# TTR87557913_done.net
KiCad netlist of a schematic drawn in Altium Designer
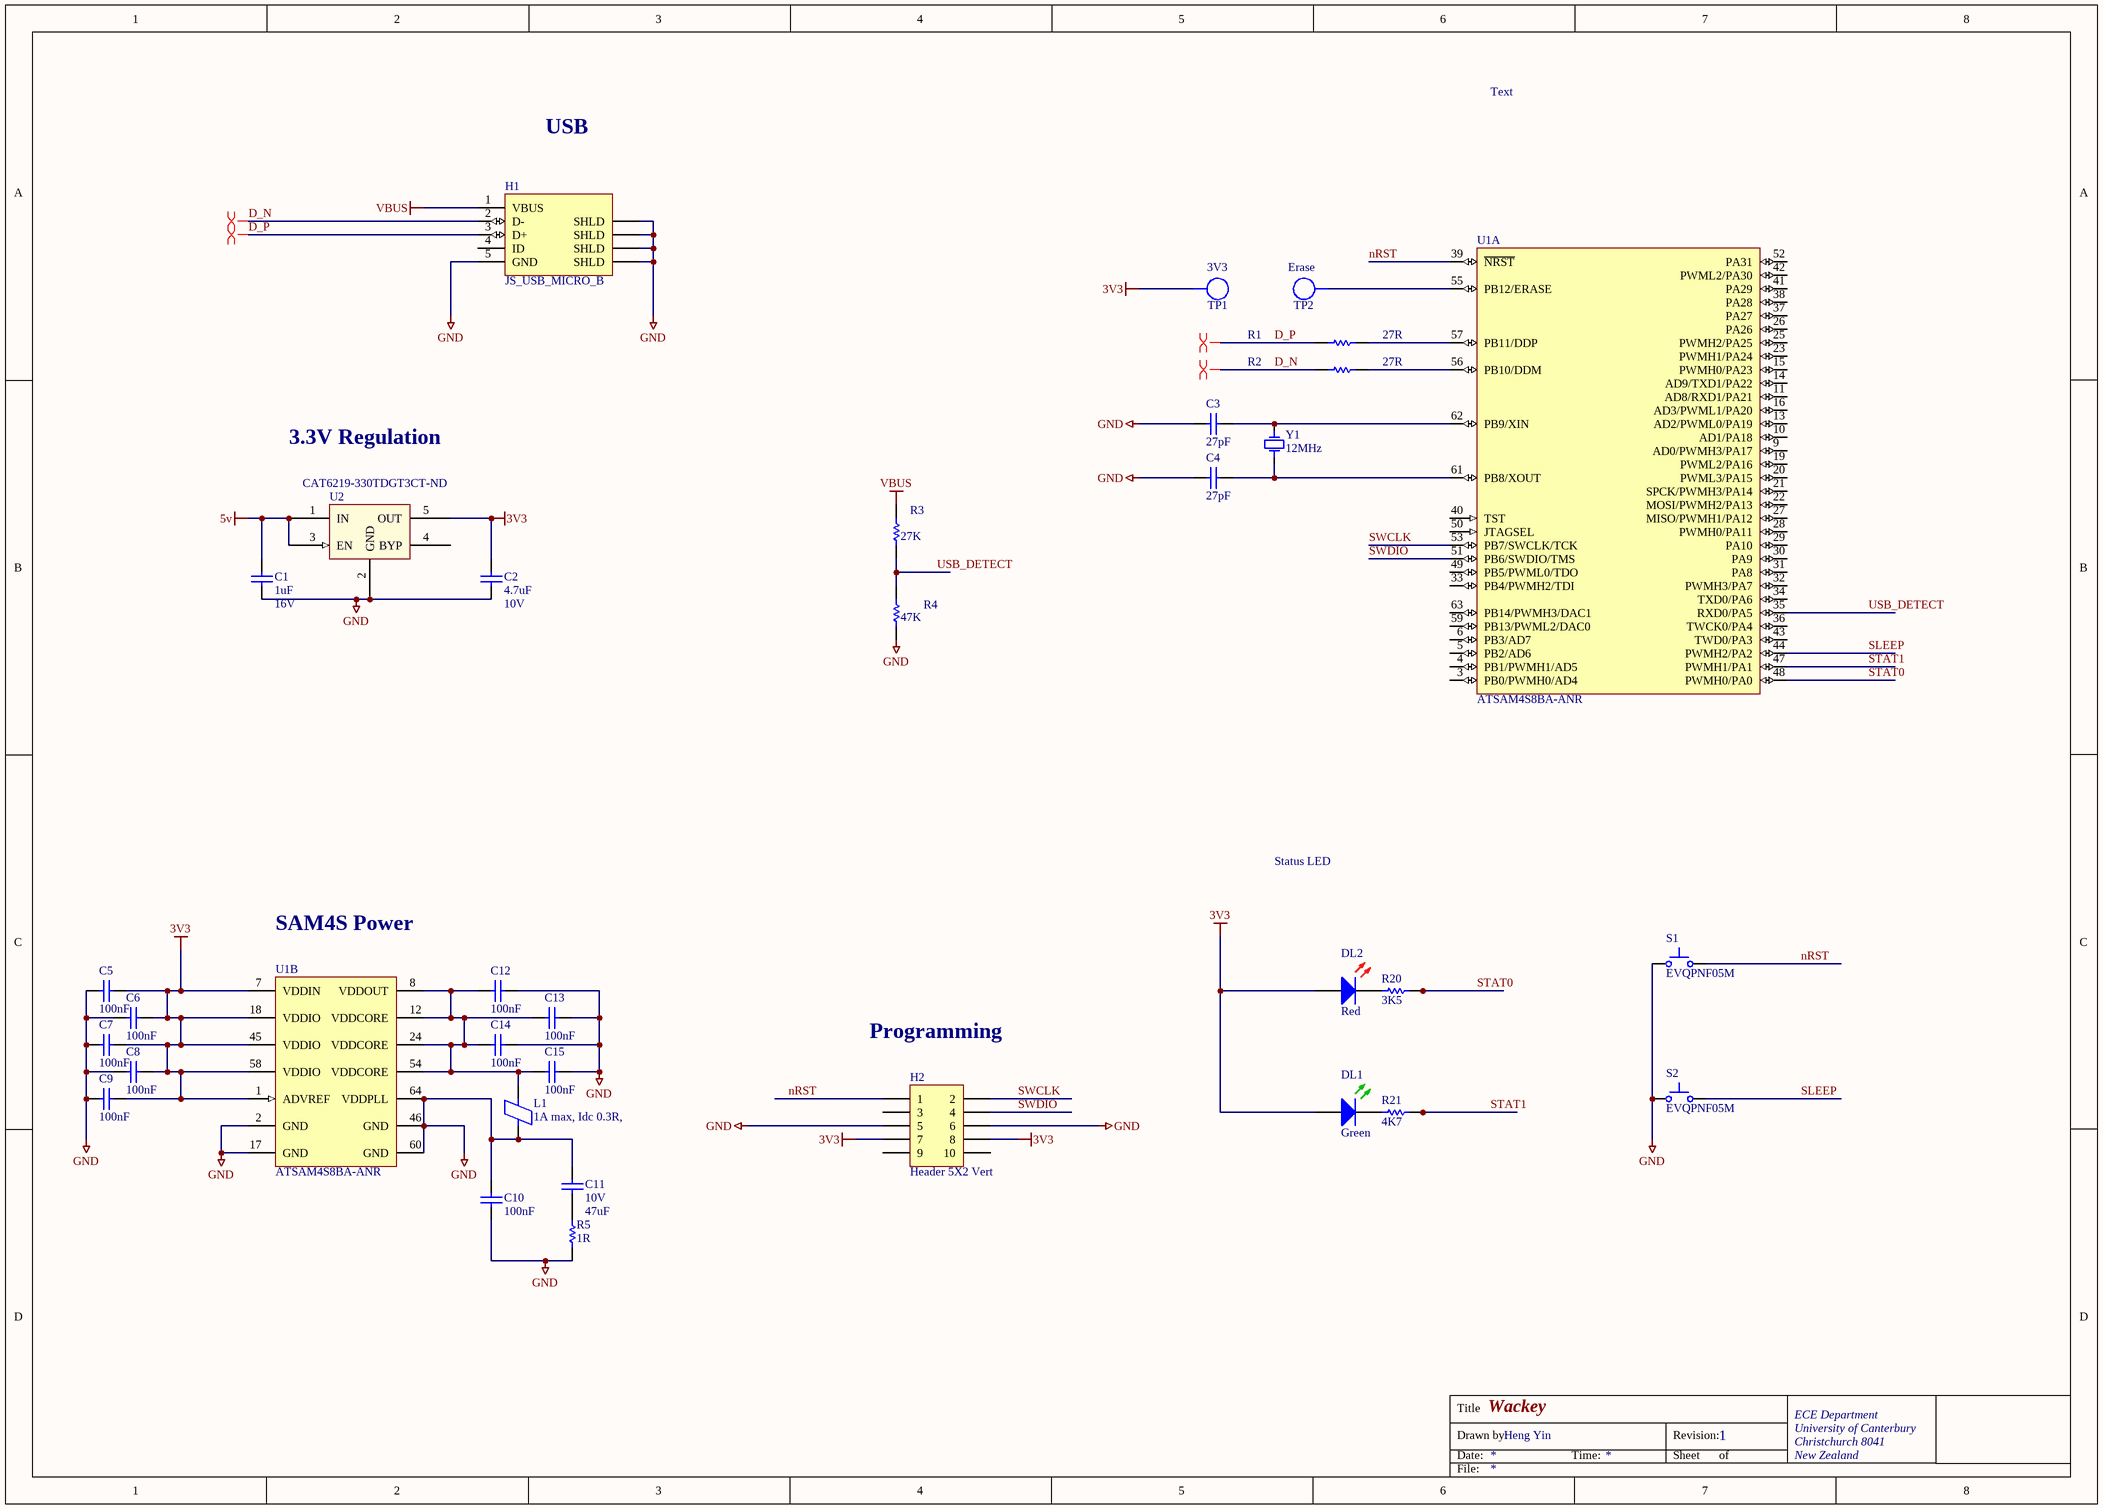
[diagram p0: TTR87557913_done.SchDoc]

(export (version "E")
  (design (tool "Eeschema 10.0.6"))
  (components
    (comp (ref "C1")
      (value "1uF")
      (footprint "CAPC1608L")
      (description "CAP CER 1uF Y5V -20% +80% 16V 0603")
      (fields (field (name "MAX VOLTAGE") "16V"))
      (libsource (lib "ECE AD19Components_22V1") (part "CC_1uF_0603"))
    )
    (comp (ref "C2")
      (value "4.7uF")
      (footprint "CAPC1608N")
      (description "CAP CER 4.7uF X5R +-20%  10V 0603")
      (fields (field (name "MAX VOLTAGE") "10V"))
      (libsource (lib "ECE AD19Components_22V1") (part "CC_4.7uF_0603"))
    )
    (comp (ref "C3")
      (value "27pF")
      (footprint "CAPC1608L")
      (description "CAP CER 27pF NPO/COG +-5% 50V 0603")
      (libsource (lib "ECE AD19Components_22V1") (part "CC_27pF_0603"))
    )
    (comp (ref "C4")
      (value "27pF")
      (footprint "CAPC1608L")
      (description "CAP CER 27pF NPO/COG +-5% 50V 0603")
      (libsource (lib "ECE AD19Components_22V1") (part "CC_27pF_0603"))
    )
    (comp (ref "C5")
      (value "100nF")
      (footprint "CAPC1608L")
      (description "CAP CER 100nF X7R +-10% 50V 0603")
      (libsource (lib "ECE AD19Components_22V1") (part "CC_100nF_0603"))
    )
    (comp (ref "C6")
      (value "100nF")
      (footprint "CAPC1608L")
      (description "CAP CER 100nF X7R +-10% 50V 0603")
      (libsource (lib "ECE AD19Components_22V1") (part "CC_100nF_0603"))
    )
    (comp (ref "C7")
      (value "100nF")
      (footprint "CAPC1608L")
      (description "CAP CER 100nF X7R +-10% 50V 0603")
      (libsource (lib "ECE AD19Components_22V1") (part "CC_100nF_0603"))
    )
    (comp (ref "C8")
      (value "100nF")
      (footprint "CAPC1608L")
      (description "CAP CER 100nF X7R +-10% 50V 0603")
      (libsource (lib "ECE AD19Components_22V1") (part "CC_100nF_0603"))
    )
    (comp (ref "C9")
      (value "100nF")
      (footprint "CAPC1608L")
      (description "CAP CER 100nF X7R +-10% 50V 0603")
      (libsource (lib "ECE AD19Components_22V1") (part "CC_100nF_0603"))
    )
    (comp (ref "C10")
      (value "100nF")
      (footprint "CAPC1608L")
      (description "CAP CER 100nF X7R +-10% 50V 0603")
      (libsource (lib "ECE AD19Components_22V1") (part "CC_100nF_0603"))
    )
    (comp (ref "C11")
      (value "47uF")
      (footprint "CAPC3216L")
      (description "CAP CER 47uF X5R -/+20% 10V 1206")
      (fields (field (name "MAX VOLTAGE") "10V"))
      (libsource (lib "ECE AD19Components_22V1") (part "CC_47uF_1206"))
    )
    (comp (ref "C12")
      (value "100nF")
      (footprint "CAPC1608L")
      (description "CAP CER 100nF X7R +-10% 50V 0603")
      (libsource (lib "ECE AD19Components_22V1") (part "CC_100nF_0603"))
    )
    (comp (ref "C13")
      (value "100nF")
      (footprint "CAPC1608L")
      (description "CAP CER 100nF X7R +-10% 50V 0603")
      (libsource (lib "ECE AD19Components_22V1") (part "CC_100nF_0603"))
    )
    (comp (ref "C14")
      (value "100nF")
      (footprint "CAPC1608L")
      (description "CAP CER 100nF X7R +-10% 50V 0603")
      (libsource (lib "ECE AD19Components_22V1") (part "CC_100nF_0603"))
    )
    (comp (ref "C15")
      (value "100nF")
      (footprint "CAPC1608L")
      (description "CAP CER 100nF X7R +-10% 50V 0603")
      (libsource (lib "ECE AD19Components_22V1") (part "CC_100nF_0603"))
    )
    (comp (ref "DL1")
      (value "Green")
      (footprint "WL-SMCW0603")
      (description "LED Green 430mcd 0603 SMD")
      (fields
        (field (name "MANUFACTURER") "WURTH ELEKTRONIK")
        (field (name "MANUFACTURER PART NUMBER") "150060GS75000")
        (field (name "LED COLOUR") "Green")
      )
      (libsource (lib "ECE AD19Components_22V1") (part "DL_150060GS75000"))
    )
    (comp (ref "DL2")
      (value "Red")
      (footprint "WL-SMCW0603")
      (description "LED Red 250mcd 0603 SMD")
      (fields
        (field (name "MANUFACTURER") "WURTH ELEKTRONIK")
        (field (name "MANUFACTURER PART NUMBER") "150060RS75000")
        (field (name "LED COLOUR") "Red")
      )
      (libsource (lib "ECE AD19Components_22V1") (part "DL_150060RS75000"))
    )
    (comp (ref "H1")
      (value "JS_USB_MICRO_B")
      (footprint "FCI_USB_10118194-0001LF")
      (description "CONN USB MICRO B RECPT SMT R/A")
      (fields (field (name "MANUFACTURER") "FCI") (field (name "MANUFACTURER PART NUMBER") "10118194-0001LF"))
      (libsource (lib "ECE AD19Components_22V1") (part "JS_USB_MICRO_B_SMT"))
    )
    (comp (ref "H2")
      (value "Header 5X2 Vert")
      (footprint "IDC2.54-V10D")
      (description "IDC Header, 2,54mm, 10-Pin, Vert")
      (libsource (lib "ECE AD19Components_22V1") (part "JA_HDR_IDC_5X2_VERT"))
    )
    (comp (ref "L1")
      (value "1A max, Idc 0.3R,")
      (footprint "INDC3216L")
      (description "Ferrite Bead, Rdc 0.3R, Z100MHZ 600R, Imax 1A, SMD 1206")
      (fields
        (field (name "MANUFACTURER") "FAIR-RITE")
        (field (name "MANUFACTURER PART NUMBER") "2512066017Y1")
      )
      (libsource (lib "ECE AD19Components_22V1") (part "IN_Ferrite-Bead"))
    )
    (comp (ref "R1")
      (value "27R")
      (footprint "RESC1608L")
      (description "RES 27 OHM 1/10W 5% 0603 SMD")
      (libsource (lib "ECE AD19Components_22V1") (part "RS_27R"))
    )
    (comp (ref "R2")
      (value "27R")
      (footprint "RESC1608L")
      (description "RES 27 OHM 1/10W 5% 0603 SMD")
      (libsource (lib "ECE AD19Components_22V1") (part "RS_27R"))
    )
    (comp (ref "R3")
      (value "27K")
      (footprint "RESC1608L")
      (description "RES 27K OHM 1/10W 5% 0603 SMD")
      (libsource (lib "ECE AD19Components_22V1") (part "RS_27K"))
    )
    (comp (ref "R4")
      (value "47K")
      (footprint "RESC1608N")
      (description "RES 47.0K OHM 1/10W 5% 0603 SMD")
      (libsource (lib "ECE AD19Components_22V1") (part "RS_47K"))
    )
    (comp (ref "R5")
      (value "1R")
      (footprint "RESC3216L")
      (description "RES 1R OHM 1/4W 5% 1206 SMD")
      (libsource (lib "ECE AD19Components_22V1") (part "RT_1R"))
    )
    (comp (ref "R20")
      (value "3K5")
      (footprint "RESC1608L")
      (description "RES 4.7K OHM 1/10W 5% 0603 SMD")
      (libsource (lib "ECE AD19Components_22V1") (part "RS_4K7"))
    )
    (comp (ref "R21")
      (value "4K7")
      (footprint "RESC1608L")
      (description "RES 4.7K OHM 1/10W 5% 0603 SMD")
      (libsource (lib "ECE AD19Components_22V1") (part "RS_4K7"))
    )
    (comp (ref "S1")
      (value "EVQPNF05M")
      (footprint "EVQPNF05M")
      (description "Panasonic 6 x 3.5mm SMD Light Touch Switch Type SMD")
      (fields (field (name "MANUFACTURER") "Panasonic"))
      (libsource (lib "ECE AD19Components_22V1") (part "WS_EVQPNF05M"))
    )
    (comp (ref "S2")
      (value "EVQPNF05M")
      (footprint "EVQPNF05M")
      (description "Panasonic 6 x 3.5mm SMD Light Touch Switch Type SMD")
      (fields (field (name "MANUFACTURER") "Panasonic"))
      (libsource (lib "ECE AD19Components_22V1") (part "WS_EVQPNF05M"))
    )
    (comp (ref "TP1")
      (value "TP")
      (footprint "TP_1206")
      (description "Test-Point 3.3x1.6x2.1mm SMD")
      (fields
        (field (name "MANUFACTURER") "Harwin Inc")
        (field (name "MANUFACTURER PART NUMBER") "S1751-46R")
      )
      (libsource (lib "ECE AD19Components_22V1") (part "TP_1206"))
    )
    (comp (ref "TP2")
      (value "TP")
      (footprint "TP_1206")
      (description "Test-Point 3.3x1.6x2.1mm SMD")
      (fields
        (field (name "MANUFACTURER") "Harwin Inc")
        (field (name "MANUFACTURER PART NUMBER") "S1751-46R")
      )
      (libsource (lib "ECE AD19Components_22V1") (part "TP_1206"))
    )
    (comp (ref "U1")
      (value "ATSAM4S8BA-ANR")
      (footprint "LQFP64_L")
      (description "IC MCU 32BIT 512KB FLASH 64LQFP")
      (fields (field (name "MANUFACTURER") "Atmel"))
      (libsource (lib "ECE AD19Components_22V1") (part "SE_ATSAM4S16BA-MU"))
    )
    (comp (ref "U2")
      (value "CAT6219-330TDGT3")
      (footprint "SOT95P280X145-5N")
      (description "IC REG LIN 3.3V 500MA TSOT23-5")
      (fields
        (field (name "BASE PART NUMBER") "CAT6219")
        (field (name "SUPPLIER PART NUMBER") "CAT6219-330TDGT3CT-ND")
      )
      (libsource (lib "ENCE461AD19_V23") (part "SV_CAT6219-330TDGT3"))
    )
    (comp (ref "Y1")
      (value "12MHz")
      (footprint "6.0X3.5-4")
      (description "CRYSTAL 12MHZ 18PF 6X3.5mm SMD")
      (fields
        (field (name "MANUFACTURER") "CTS-Frequency Controls")
        (field (name "MANUFACTURER PART NUMBER") "406C35D12M00000")
        (field (name "FREQUENCY") "12MHz")
      )
      (libsource (lib "ECE AD19Components_22V1") (part "XT_CRYSTAL_12MHz_18pF"))
    )
  )
  (nets
    (net (code "1") (name "/D_N") (class "Default")
      (node (ref "H1") (pin "2") (pinfunction "D-_2") (pintype "bidirectional"))
      (node (ref "R2") (pin "1") (pinfunction "1_1") (pintype "passive"))
    )
    (net (code "2") (name "/D_P") (class "Default")
      (node (ref "H1") (pin "3") (pinfunction "D+_3") (pintype "bidirectional"))
      (node (ref "R1") (pin "1") (pinfunction "1_1") (pintype "passive"))
    )
    (net (code "3") (name "/SLEEP") (class "Default")
      (node (ref "S2") (pin "2") (pintype "passive"))
      (node (ref "U1") (pin "44") (pinfunction "PWMH2/PA2_44") (pintype "bidirectional"))
    )
    (net (code "4") (name "/STAT0") (class "Default")
      (node (ref "R20") (pin "2") (pinfunction "2_2") (pintype "passive"))
      (node (ref "U1") (pin "48") (pinfunction "PWMH0/PA0_48") (pintype "bidirectional"))
    )
    (net (code "5") (name "/STAT1") (class "Default")
      (node (ref "R21") (pin "2") (pinfunction "2_2") (pintype "passive"))
      (node (ref "U1") (pin "47") (pinfunction "PWMH1/PA1_47") (pintype "bidirectional"))
    )
    (net (code "6") (name "/SWCLK") (class "Default")
      (node (ref "H2") (pin "2") (pinfunction "2_2") (pintype "passive"))
      (node (ref "U1") (pin "53") (pinfunction "PB7/SWCLK/TCK_53") (pintype "bidirectional"))
    )
    (net (code "7") (name "/SWDIO") (class "Default")
      (node (ref "H2") (pin "4") (pinfunction "4_4") (pintype "passive"))
      (node (ref "U1") (pin "51") (pinfunction "PB6/SWDIO/TMS_51") (pintype "bidirectional"))
    )
    (net (code "8") (name "/USB_DETECT") (class "Default")
      (node (ref "R3") (pin "1") (pinfunction "1_1") (pintype "passive"))
      (node (ref "R4") (pin "2") (pinfunction "2_2") (pintype "passive"))
      (node (ref "U1") (pin "35") (pinfunction "RXD0/PA5_35") (pintype "bidirectional"))
    )
    (net (code "9") (name "/nRST") (class "Default")
      (node (ref "H2") (pin "1") (pinfunction "1_1") (pintype "passive"))
      (node (ref "S1") (pin "2") (pintype "passive"))
      (node (ref "U1") (pin "39") (pinfunction "~{NRST}_39") (pintype "bidirectional"))
    )
    (net (code "10") (name "3V3") (class "Default")
      (node (ref "C2") (pin "2") (pinfunction "2_2") (pintype "passive"))
      (node (ref "C5") (pin "2") (pinfunction "2_2") (pintype "passive"))
      (node (ref "C6") (pin "2") (pinfunction "2_2") (pintype "passive"))
      (node (ref "C7") (pin "2") (pinfunction "2_2") (pintype "passive"))
      (node (ref "C8") (pin "2") (pinfunction "2_2") (pintype "passive"))
      (node (ref "C9") (pin "1") (pinfunction "1_1") (pintype "passive"))
      (node (ref "DL1") (pin "2") (pinfunction "A_2") (pintype "passive"))
      (node (ref "DL2") (pin "2") (pinfunction "A_2") (pintype "passive"))
      (node (ref "H2") (pin "7") (pinfunction "7_7") (pintype "passive"))
      (node (ref "H2") (pin "8") (pinfunction "8_8") (pintype "passive"))
      (node (ref "TP1") (pin "1") (pinfunction "1_1") (pintype "passive"))
      (node (ref "U1") (pin "1") (pinfunction "ADVREF_1") (pintype "input"))
      (node (ref "U1") (pin "18") (pinfunction "VDDIO_18") (pintype "power_in"))
      (node (ref "U1") (pin "45") (pinfunction "VDDIO_45") (pintype "power_in"))
      (node (ref "U1") (pin "58") (pinfunction "VDDIO_58") (pintype "power_in"))
      (node (ref "U1") (pin "7") (pinfunction "VDDIN_7") (pintype "power_in"))
      (node (ref "U2") (pin "5") (pinfunction "OUT_5") (pintype "power_in"))
    )
    (net (code "11") (name "5v") (class "Default")
      (node (ref "C1") (pin "2") (pinfunction "2_2") (pintype "passive"))
      (node (ref "U2") (pin "1") (pinfunction "IN_1") (pintype "power_in"))
      (node (ref "U2") (pin "3") (pinfunction "EN_3") (pintype "input"))
    )
    (net (code "12") (name "GND") (class "Default")
      (node (ref "C1") (pin "1") (pinfunction "1_1") (pintype "passive"))
      (node (ref "C10") (pin "1") (pinfunction "1_1") (pintype "passive"))
      (node (ref "C10") (pin "2") (pinfunction "2_2") (pintype "passive"))
      (node (ref "C11") (pin "2") (pinfunction "2_2") (pintype "passive"))
      (node (ref "C12") (pin "2") (pinfunction "2_2") (pintype "passive"))
      (node (ref "C13") (pin "2") (pinfunction "2_2") (pintype "passive"))
      (node (ref "C14") (pin "2") (pinfunction "2_2") (pintype "passive"))
      (node (ref "C15") (pin "2") (pinfunction "2_2") (pintype "passive"))
      (node (ref "C2") (pin "1") (pinfunction "1_1") (pintype "passive"))
      (node (ref "C3") (pin "1") (pinfunction "1_1") (pintype "passive"))
      (node (ref "C4") (pin "1") (pinfunction "1_1") (pintype "passive"))
      (node (ref "C5") (pin "1") (pinfunction "1_1") (pintype "passive"))
      (node (ref "C6") (pin "1") (pinfunction "1_1") (pintype "passive"))
      (node (ref "C7") (pin "1") (pinfunction "1_1") (pintype "passive"))
      (node (ref "C8") (pin "1") (pinfunction "1_1") (pintype "passive"))
      (node (ref "C9") (pin "2") (pinfunction "2_2") (pintype "passive"))
      (node (ref "H1") (pin "5") (pinfunction "GND_5") (pintype "passive"))
      (node (ref "H1") (pin "6") (pinfunction "SHLD_6") (pintype "passive"))
      (node (ref "H2") (pin "5") (pinfunction "5_5") (pintype "passive"))
      (node (ref "H2") (pin "6") (pinfunction "6_6") (pintype "passive"))
      (node (ref "L1") (pin "1") (pinfunction "1_1") (pintype "passive"))
      (node (ref "R4") (pin "1") (pinfunction "1_1") (pintype "passive"))
      (node (ref "R5") (pin "1") (pinfunction "1_1") (pintype "passive"))
      (node (ref "S1") (pin "1") (pintype "passive"))
      (node (ref "S2") (pin "1") (pintype "passive"))
      (node (ref "U1") (pin "17") (pinfunction "GND_17") (pintype "power_in"))
      (node (ref "U1") (pin "2") (pinfunction "GND_2") (pintype "power_in"))
      (node (ref "U1") (pin "46") (pinfunction "GND_46") (pintype "power_in"))
      (node (ref "U1") (pin "60") (pinfunction "GND_60") (pintype "power_in"))
      (node (ref "U1") (pin "64") (pinfunction "VDDPLL_64") (pintype "power_in"))
      (node (ref "U2") (pin "2") (pinfunction "GND_2") (pintype "power_in"))
    )
    (net (code "13") (name "Net-(C11-Pad1)") (class "Default")
      (node (ref "C11") (pin "1") (pinfunction "1_1") (pintype "passive"))
      (node (ref "R5") (pin "2") (pinfunction "2_2") (pintype "passive"))
    )
    (net (code "14") (name "Net-(U1A-PB8{slash}XOUT)") (class "Default")
      (node (ref "C4") (pin "2") (pinfunction "2_2") (pintype "passive"))
      (node (ref "U1") (pin "61") (pinfunction "PB8/XOUT_61") (pintype "bidirectional"))
      (node (ref "Y1") (pin "1") (pinfunction "OSC1_1") (pintype "passive"))
    )
    (net (code "15") (name "Net-(U1A-PB9{slash}XIN)") (class "Default")
      (node (ref "C3") (pin "2") (pinfunction "2_2") (pintype "passive"))
      (node (ref "U1") (pin "62") (pinfunction "PB9/XIN_62") (pintype "bidirectional"))
      (node (ref "Y1") (pin "3") (pinfunction "OSC2_3") (pintype "passive"))
    )
    (net (code "16") (name "Net-(U1A-PB10{slash}DDM)") (class "Default")
      (node (ref "R2") (pin "2") (pinfunction "2_2") (pintype "passive"))
      (node (ref "U1") (pin "56") (pinfunction "PB10/DDM_56") (pintype "bidirectional"))
    )
    (net (code "17") (name "Net-(U1A-PB11{slash}DDP)") (class "Default")
      (node (ref "R1") (pin "2") (pinfunction "2_2") (pintype "passive"))
      (node (ref "U1") (pin "57") (pinfunction "PB11/DDP_57") (pintype "bidirectional"))
    )
    (net (code "18") (name "Net-(U1A-PB12{slash}ERASE)") (class "Default")
      (node (ref "TP2") (pin "1") (pinfunction "1_1") (pintype "passive"))
      (node (ref "U1") (pin "55") (pinfunction "PB12/ERASE_55") (pintype "bidirectional"))
    )
    (net (code "19") (name "Net-(U1B-VDDOUT)") (class "Default")
      (node (ref "C12") (pin "1") (pinfunction "1_1") (pintype "passive"))
      (node (ref "C13") (pin "1") (pinfunction "1_1") (pintype "passive"))
      (node (ref "C14") (pin "1") (pinfunction "1_1") (pintype "passive"))
      (node (ref "C15") (pin "1") (pinfunction "1_1") (pintype "passive"))
      (node (ref "L1") (pin "2") (pinfunction "2_2") (pintype "passive"))
      (node (ref "U1") (pin "12") (pinfunction "VDDCORE_12") (pintype "power_in"))
      (node (ref "U1") (pin "24") (pinfunction "VDDCORE_24") (pintype "power_in"))
      (node (ref "U1") (pin "54") (pinfunction "VDDCORE_54") (pintype "power_in"))
      (node (ref "U1") (pin "8") (pinfunction "VDDOUT_8") (pintype "power_in"))
    )
    (net (code "20") (name "VBUS") (class "Default")
      (node (ref "H1") (pin "1") (pinfunction "VBUS_1") (pintype "power_in"))
      (node (ref "R3") (pin "2") (pinfunction "2_2") (pintype "passive"))
    )
    (net (code "21") (name "unconnected-(DL1-K-Pad1)") (class "Default")
      (node (ref "DL1") (pin "1") (pinfunction "K_1") (pintype "passive"))
    )
    (net (code "22") (name "unconnected-(DL2-K-Pad1)") (class "Default")
      (node (ref "DL2") (pin "1") (pinfunction "K_1") (pintype "passive"))
    )
    (net (code "23") (name "unconnected-(H1-ID-Pad4)") (class "Default")
      (node (ref "H1") (pin "4") (pinfunction "ID_4") (pintype "power_in"))
    )
    (net (code "24") (name "unconnected-(H2-Pad3)") (class "Default")
      (node (ref "H2") (pin "3") (pinfunction "3_3") (pintype "passive"))
    )
    (net (code "25") (name "unconnected-(H2-Pad9)") (class "Default")
      (node (ref "H2") (pin "9") (pinfunction "9_9") (pintype "passive"))
    )
    (net (code "26") (name "unconnected-(H2-Pad10)") (class "Default")
      (node (ref "H2") (pin "10") (pinfunction "10_10") (pintype "passive"))
    )
    (net (code "27") (name "unconnected-(R20-Pad1)") (class "Default")
      (node (ref "R20") (pin "1") (pinfunction "1_1") (pintype "passive"))
    )
    (net (code "28") (name "unconnected-(R21-Pad1)") (class "Default")
      (node (ref "R21") (pin "1") (pinfunction "1_1") (pintype "passive"))
    )
    (net (code "29") (name "unconnected-(U1A-AD0{slash}PWMH3{slash}PA17-Pad9)") (class "Default")
      (node (ref "U1") (pin "9") (pinfunction "AD0/PWMH3/PA17_9") (pintype "bidirectional"))
    )
    (net (code "30") (name "unconnected-(U1A-AD1{slash}PA18-Pad10)") (class "Default")
      (node (ref "U1") (pin "10") (pinfunction "AD1/PA18_10") (pintype "bidirectional"))
    )
    (net (code "31") (name "unconnected-(U1A-AD2{slash}PWML0{slash}PA19-Pad13)") (class "Default")
      (node (ref "U1") (pin "13") (pinfunction "AD2/PWML0/PA19_13") (pintype "bidirectional"))
    )
    (net (code "32") (name "unconnected-(U1A-AD3{slash}PWML1{slash}PA20-Pad16)") (class "Default")
      (node (ref "U1") (pin "16") (pinfunction "AD3/PWML1/PA20_16") (pintype "bidirectional"))
    )
    (net (code "33") (name "unconnected-(U1A-AD8{slash}RXD1{slash}PA21-Pad11)") (class "Default")
      (node (ref "U1") (pin "11") (pinfunction "AD8/RXD1/PA21_11") (pintype "bidirectional"))
    )
    (net (code "34") (name "unconnected-(U1A-AD9{slash}TXD1{slash}PA22-Pad14)") (class "Default")
      (node (ref "U1") (pin "14") (pinfunction "AD9/TXD1/PA22_14") (pintype "bidirectional"))
    )
    (net (code "35") (name "unconnected-(U1A-JTAGSEL-Pad50)") (class "Default")
      (node (ref "U1") (pin "50") (pinfunction "JTAGSEL_50") (pintype "input"))
    )
    (net (code "36") (name "unconnected-(U1A-MISO{slash}PWMH1{slash}PA12-Pad27)") (class "Default")
      (node (ref "U1") (pin "27") (pinfunction "MISO/PWMH1/PA12_27") (pintype "bidirectional"))
    )
    (net (code "37") (name "unconnected-(U1A-MOSI{slash}PWMH2{slash}PA13-Pad22)") (class "Default")
      (node (ref "U1") (pin "22") (pinfunction "MOSI/PWMH2/PA13_22") (pintype "bidirectional"))
    )
    (net (code "38") (name "unconnected-(U1A-PA8-Pad31)") (class "Default")
      (node (ref "U1") (pin "31") (pinfunction "PA8_31") (pintype "bidirectional"))
    )
    (net (code "39") (name "unconnected-(U1A-PA9-Pad30)") (class "Default")
      (node (ref "U1") (pin "30") (pinfunction "PA9_30") (pintype "bidirectional"))
    )
    (net (code "40") (name "unconnected-(U1A-PA10-Pad29)") (class "Default")
      (node (ref "U1") (pin "29") (pinfunction "PA10_29") (pintype "bidirectional"))
    )
    (net (code "41") (name "unconnected-(U1A-PA26-Pad26)") (class "Default")
      (node (ref "U1") (pin "26") (pinfunction "PA26_26") (pintype "bidirectional"))
    )
    (net (code "42") (name "unconnected-(U1A-PA27-Pad37)") (class "Default")
      (node (ref "U1") (pin "37") (pinfunction "PA27_37") (pintype "bidirectional"))
    )
    (net (code "43") (name "unconnected-(U1A-PA28-Pad38)") (class "Default")
      (node (ref "U1") (pin "38") (pinfunction "PA28_38") (pintype "bidirectional"))
    )
    (net (code "44") (name "unconnected-(U1A-PA29-Pad41)") (class "Default")
      (node (ref "U1") (pin "41") (pinfunction "PA29_41") (pintype "bidirectional"))
    )
    (net (code "45") (name "unconnected-(U1A-PA31-Pad52)") (class "Default")
      (node (ref "U1") (pin "52") (pinfunction "PA31_52") (pintype "bidirectional"))
    )
    (net (code "46") (name "unconnected-(U1A-PB0{slash}PWMH0{slash}AD4-Pad3)") (class "Default")
      (node (ref "U1") (pin "3") (pinfunction "PB0/PWMH0/AD4_3") (pintype "bidirectional"))
    )
    (net (code "47") (name "unconnected-(U1A-PB1{slash}PWMH1{slash}AD5-Pad4)") (class "Default")
      (node (ref "U1") (pin "4") (pinfunction "PB1/PWMH1/AD5_4") (pintype "bidirectional"))
    )
    (net (code "48") (name "unconnected-(U1A-PB2{slash}AD6-Pad5)") (class "Default")
      (node (ref "U1") (pin "5") (pinfunction "PB2/AD6_5") (pintype "bidirectional"))
    )
    (net (code "49") (name "unconnected-(U1A-PB3{slash}AD7-Pad6)") (class "Default")
      (node (ref "U1") (pin "6") (pinfunction "PB3/AD7_6") (pintype "bidirectional"))
    )
    (net (code "50") (name "unconnected-(U1A-PB4{slash}PWMH2{slash}TDI-Pad33)") (class "Default")
      (node (ref "U1") (pin "33") (pinfunction "PB4/PWMH2/TDI_33") (pintype "bidirectional"))
    )
    (net (code "51") (name "unconnected-(U1A-PB5{slash}PWML0{slash}TDO-Pad49)") (class "Default")
      (node (ref "U1") (pin "49") (pinfunction "PB5/PWML0/TDO_49") (pintype "bidirectional"))
    )
    (net (code "52") (name "unconnected-(U1A-PB13{slash}PWML2{slash}DAC0-Pad59)") (class "Default")
      (node (ref "U1") (pin "59") (pinfunction "PB13/PWML2/DAC0_59") (pintype "bidirectional"))
    )
    (net (code "53") (name "unconnected-(U1A-PB14{slash}PWMH3{slash}DAC1-Pad63)") (class "Default")
      (node (ref "U1") (pin "63") (pinfunction "PB14/PWMH3/DAC1_63") (pintype "bidirectional"))
    )
    (net (code "54") (name "unconnected-(U1A-PWMH0{slash}PA11-Pad28)") (class "Default")
      (node (ref "U1") (pin "28") (pinfunction "PWMH0/PA11_28") (pintype "bidirectional"))
    )
    (net (code "55") (name "unconnected-(U1A-PWMH0{slash}PA23-Pad15)") (class "Default")
      (node (ref "U1") (pin "15") (pinfunction "PWMH0/PA23_15") (pintype "bidirectional"))
    )
    (net (code "56") (name "unconnected-(U1A-PWMH1{slash}PA24-Pad23)") (class "Default")
      (node (ref "U1") (pin "23") (pinfunction "PWMH1/PA24_23") (pintype "bidirectional"))
    )
    (net (code "57") (name "unconnected-(U1A-PWMH2{slash}PA25-Pad25)") (class "Default")
      (node (ref "U1") (pin "25") (pinfunction "PWMH2/PA25_25") (pintype "bidirectional"))
    )
    (net (code "58") (name "unconnected-(U1A-PWMH3{slash}PA7-Pad32)") (class "Default")
      (node (ref "U1") (pin "32") (pinfunction "PWMH3/PA7_32") (pintype "bidirectional"))
    )
    (net (code "59") (name "unconnected-(U1A-PWML2{slash}PA16-Pad19)") (class "Default")
      (node (ref "U1") (pin "19") (pinfunction "PWML2/PA16_19") (pintype "bidirectional"))
    )
    (net (code "60") (name "unconnected-(U1A-PWML2{slash}PA30-Pad42)") (class "Default")
      (node (ref "U1") (pin "42") (pinfunction "PWML2/PA30_42") (pintype "bidirectional"))
    )
    (net (code "61") (name "unconnected-(U1A-PWML3{slash}PA15-Pad20)") (class "Default")
      (node (ref "U1") (pin "20") (pinfunction "PWML3/PA15_20") (pintype "bidirectional"))
    )
    (net (code "62") (name "unconnected-(U1A-SPCK{slash}PWMH3{slash}PA14-Pad21)") (class "Default")
      (node (ref "U1") (pin "21") (pinfunction "SPCK/PWMH3/PA14_21") (pintype "bidirectional"))
    )
    (net (code "63") (name "unconnected-(U1A-TST-Pad40)") (class "Default")
      (node (ref "U1") (pin "40") (pinfunction "TST_40") (pintype "input"))
    )
    (net (code "64") (name "unconnected-(U1A-TWCK0{slash}PA4-Pad36)") (class "Default")
      (node (ref "U1") (pin "36") (pinfunction "TWCK0/PA4_36") (pintype "bidirectional"))
    )
    (net (code "65") (name "unconnected-(U1A-TWD0{slash}PA3-Pad43)") (class "Default")
      (node (ref "U1") (pin "43") (pinfunction "TWD0/PA3_43") (pintype "bidirectional"))
    )
    (net (code "66") (name "unconnected-(U1A-TXD0{slash}PA6-Pad34)") (class "Default")
      (node (ref "U1") (pin "34") (pinfunction "TXD0/PA6_34") (pintype "bidirectional"))
    )
    (net (code "67") (name "unconnected-(U2-BYP-Pad4)") (class "Default")
      (node (ref "U2") (pin "4") (pinfunction "BYP_4") (pintype "passive"))
    )
  )
)
